# LearnToSolder.net
KiCad netlist of a schematic drawn in EAGLE
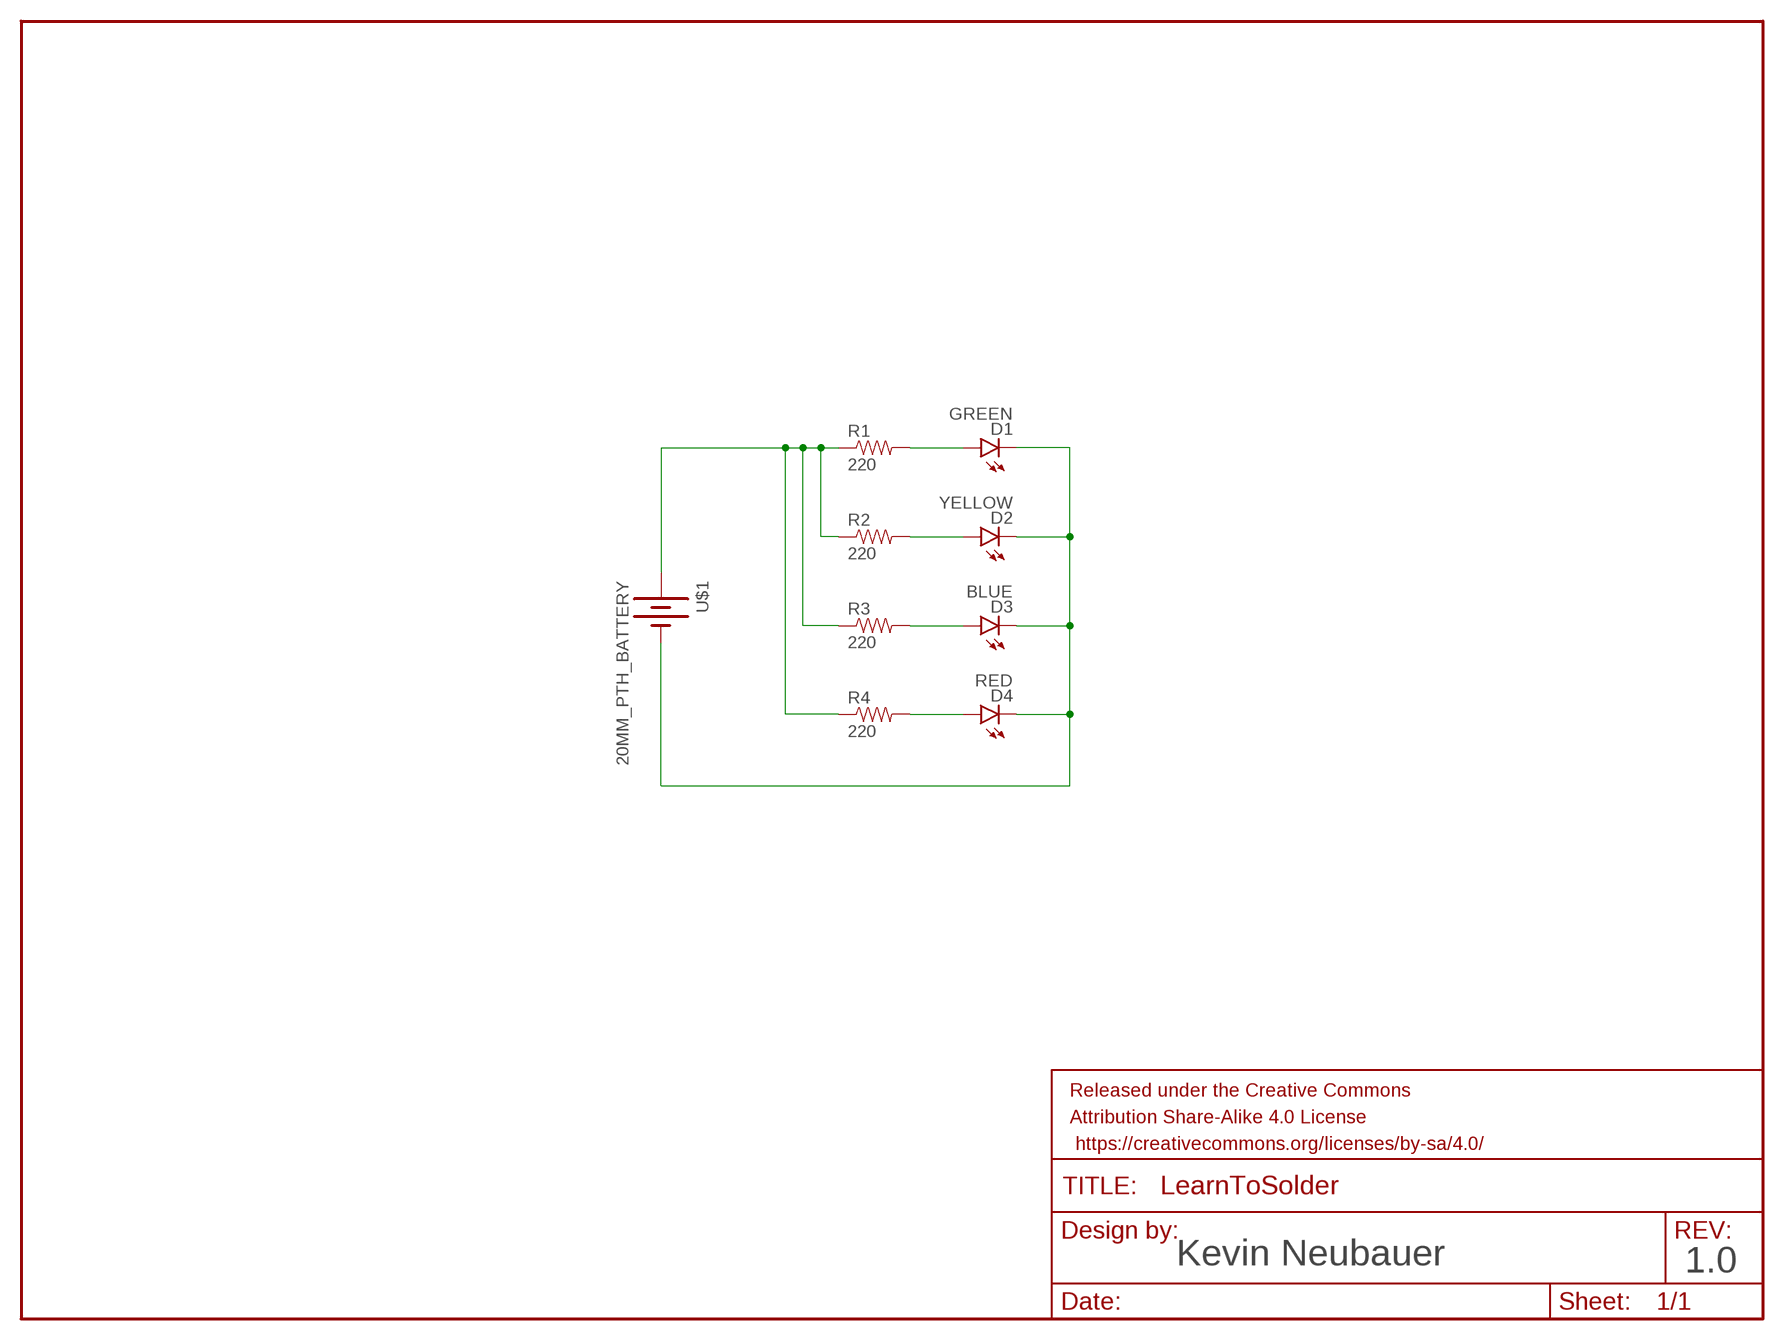
[diagram p0: schematic, sheet 1]

(export (version "E")
  (design (tool "Eeschema 10.0.6"))
  (components
    (comp (ref "D1")
      (value "GREEN")
      (footprint "eagle-import:LED5MM")
      (libsource (lib "eagle-import") (part "LED5MM"))
    )
    (comp (ref "D2")
      (value "YELLOW")
      (footprint "eagle-import:LED5MM")
      (libsource (lib "eagle-import") (part "LED5MM"))
    )
    (comp (ref "D3")
      (value "BLUE")
      (footprint "eagle-import:LED5MM")
      (libsource (lib "eagle-import") (part "LED5MM"))
    )
    (comp (ref "D4")
      (value "RED")
      (footprint "eagle-import:LED5MM")
      (libsource (lib "eagle-import") (part "LED5MM"))
    )
    (comp (ref "FRAME1")
      (value "FRAME-LETTER")
      (footprint "eagle-import:CREATIVE_COMMONS")
      (libsource (lib "eagle-import") (part "FRAME-LETTER"))
    )
    (comp (ref "R1")
      (value "220")
      (footprint "eagle-import:AXIAL-0.4")
      (libsource (lib "eagle-import") (part "RESISTORPTH-1/4W"))
    )
    (comp (ref "R2")
      (value "220")
      (footprint "eagle-import:AXIAL-0.4")
      (libsource (lib "eagle-import") (part "RESISTORPTH-1/4W"))
    )
    (comp (ref "R3")
      (value "220")
      (footprint "eagle-import:AXIAL-0.4")
      (libsource (lib "eagle-import") (part "RESISTORPTH-1/4W"))
    )
    (comp (ref "R4")
      (value "220")
      (footprint "eagle-import:AXIAL-0.4")
      (libsource (lib "eagle-import") (part "RESISTORPTH-1/4W"))
    )
    (comp (ref "U$1")
      (value "20MM_PTH_BATTERY")
      (footprint "eagle-import:20MM_PTH_CR2032")
      (libsource (lib "eagle-import") (part "20MM_PTH_BATTERY"))
    )
  )
  (nets
    (net (code "1") (name "Net-(D1-C)") (class "Default")
      (node (ref "D1") (pin "K") (pinfunction "C_K") (pintype "passive"))
      (node (ref "D2") (pin "K") (pinfunction "C_K") (pintype "passive"))
      (node (ref "D3") (pin "K") (pinfunction "C_K") (pintype "passive"))
      (node (ref "D4") (pin "K") (pinfunction "C_K") (pintype "passive"))
      (node (ref "U$1") (pin "2") (pinfunction "-_2") (pintype "power_in"))
    )
    (net (code "2") (name "Net-(R1-1)") (class "Default")
      (node (ref "R1") (pin "P$1") (pinfunction "1_P$1") (pintype "passive"))
      (node (ref "R2") (pin "P$1") (pinfunction "1_P$1") (pintype "passive"))
      (node (ref "R3") (pin "P$1") (pinfunction "1_P$1") (pintype "passive"))
      (node (ref "R4") (pin "P$1") (pinfunction "1_P$1") (pintype "passive"))
      (node (ref "U$1") (pin "1") (pinfunction "+_1") (pintype "power_in"))
      (node (ref "U$1") (pin "3") (pinfunction "+_3") (pintype "power_in"))
    )
    (net (code "3") (name "Net-(R1-2)") (class "Default")
      (node (ref "D1") (pin "A") (pinfunction "A_A") (pintype "passive"))
      (node (ref "R1") (pin "P$2") (pinfunction "2_P$2") (pintype "passive"))
    )
    (net (code "4") (name "Net-(R2-2)") (class "Default")
      (node (ref "D2") (pin "A") (pinfunction "A_A") (pintype "passive"))
      (node (ref "R2") (pin "P$2") (pinfunction "2_P$2") (pintype "passive"))
    )
    (net (code "5") (name "Net-(R3-2)") (class "Default")
      (node (ref "D3") (pin "A") (pinfunction "A_A") (pintype "passive"))
      (node (ref "R3") (pin "P$2") (pinfunction "2_P$2") (pintype "passive"))
    )
    (net (code "6") (name "Net-(R4-2)") (class "Default")
      (node (ref "D4") (pin "A") (pinfunction "A_A") (pintype "passive"))
      (node (ref "R4") (pin "P$2") (pinfunction "2_P$2") (pintype "passive"))
    )
  )
)
